# pripherals.net
KiCad netlist of a schematic drawn in Altium Designer
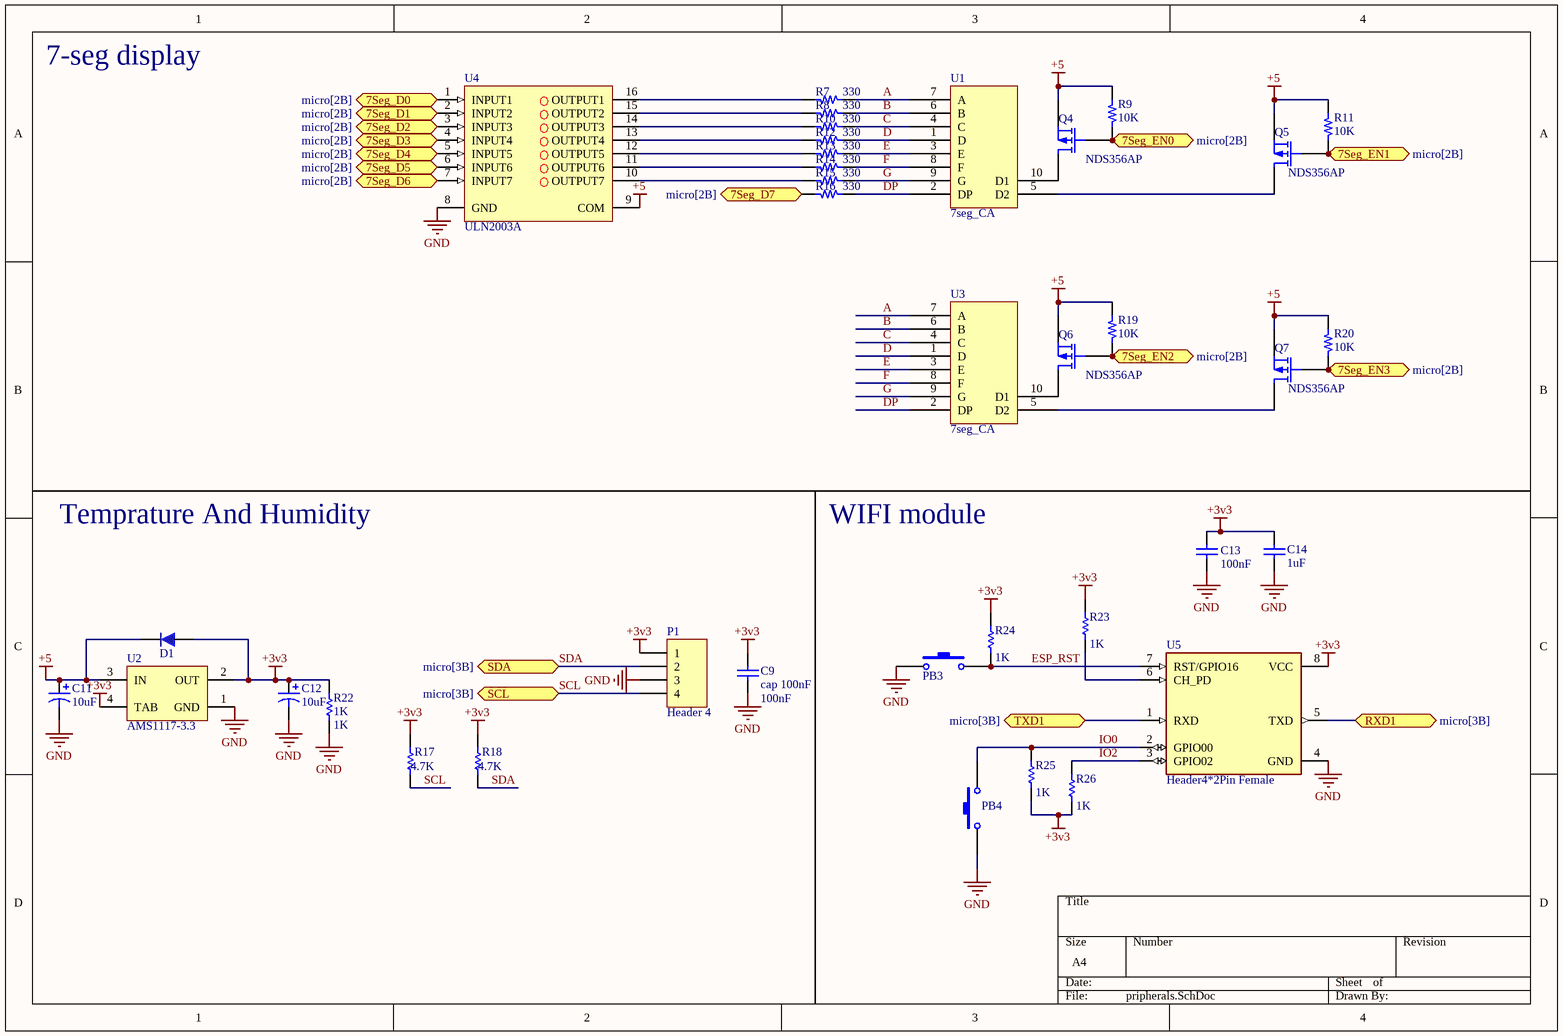
[diagram p0: pripherals.SchDoc]

(export (version "E")
  (design (tool "Eeschema 10.0.6"))
  (components
    (comp (ref "C9")
      (value "cap 100nF")
      (footprint "Cap 805")
      (description "Capacitor")
      (fields (field (name "ALTIUM_VALUE") "100nF") (field (name "PUBLISHER") "Altium Limited"))
      (libsource (lib "Miscellaneous Devices") (part "Cap"))
    )
    (comp (ref "C11")
      (value "10uF")
      (footprint "CAP0805")
      (description "CAP seramic")
      (fields (field (name "Comment") "cap 10uF") (field (name "PUBLISHER") "Altium Limited"))
      (libsource (lib "Miscellaneous Devices") (part "Cap Pol1"))
    )
    (comp (ref "C12")
      (value "10uF")
      (footprint "CAP0805")
      (description "CAP seramic")
      (fields (field (name "Comment") "cap 10uF") (field (name "PUBLISHER") "Altium Limited"))
      (libsource (lib "Miscellaneous Devices") (part "Cap Pol1"))
    )
    (comp (ref "C13")
      (value "100nF")
      (footprint "CAP0805")
      (description "CAP seramic")
      (fields (field (name "Comment") "cap 100nF"))
      (libsource (lib "Altium library (www.AVRelec.com)") (part "Cap ceramic"))
    )
    (comp (ref "C14")
      (value "1uF")
      (footprint "CAP0805")
      (description "CAP seramic")
      (fields (field (name "Comment") "cap 1uF"))
      (libsource (lib "Altium library (www.AVRelec.com)") (part "Cap ceramic"))
    )
    (comp (ref "D1")
      (value "uf4007")
      (footprint "DIOM4629X24N")
      (description "Standard Rectifiers")
      (fields (field (name "MANUFACTURER") "DC COMPONENTS") (field (name "DESIGNER") "Abbas Basereh"))
      (libsource (lib "Altium (2)") (part "1n4007 SMD M7"))
    )
    (comp (ref "P1")
      (value "Header 4")
      (footprint "HDR1X4")
      (description "Header, 4-Pin")
      (fields (field (name "PUBLISHER") "Altium Limited"))
      (libsource (lib "Miscellaneous Connectors") (part "Header 4"))
    )
    (comp (ref "PB3")
      (value "Push-Button-tall")
      (footprint "tack-sw-3x5x6")
      (libsource (lib "Mine-Discreet") (part "Push-Button-tall"))
    )
    (comp (ref "PB4")
      (value "Push-Button-tall")
      (footprint "tack-sw-3x5x6")
      (libsource (lib "Mine-Discreet") (part "Push-Button-tall"))
    )
    (comp (ref "Q4")
      (value "NDS356AP")
      (footprint "soT95p280x130-3n")
      (description "P-Channel MOSFET SOT23")
      (fields (field (name "PUBLISHER") "Altium Limited"))
      (libsource (lib "Miscellaneous Devices") (part "MOSFET-P"))
    )
    (comp (ref "Q5")
      (value "NDS356AP")
      (footprint "soT95p280x130-3n")
      (description "P-Channel MOSFET SOT23")
      (fields (field (name "PUBLISHER") "Altium Limited"))
      (libsource (lib "Miscellaneous Devices") (part "MOSFET-P"))
    )
    (comp (ref "Q6")
      (value "NDS356AP")
      (footprint "soT95p280x130-3n")
      (description "P-Channel MOSFET SOT23")
      (fields (field (name "PUBLISHER") "Altium Limited"))
      (libsource (lib "Miscellaneous Devices") (part "MOSFET-P"))
    )
    (comp (ref "Q7")
      (value "NDS356AP")
      (footprint "soT95p280x130-3n")
      (description "P-Channel MOSFET SOT23")
      (fields (field (name "PUBLISHER") "Altium Limited"))
      (libsource (lib "Miscellaneous Devices") (part "MOSFET-P"))
    )
    (comp (ref "R7")
      (value "330")
      (footprint "RES0805")
      (description "RES SMD 0603")
      (fields (field (name "PART NUMBER") "RCS0805100KFKEA"))
      (libsource (lib "lamp control-ver2") (part "Resistor"))
    )
    (comp (ref "R8")
      (value "330")
      (footprint "RES0805")
      (description "RES SMD 0603")
      (fields (field (name "PART NUMBER") "RCS0805100KFKEA"))
      (libsource (lib "lamp control-ver2") (part "Resistor"))
    )
    (comp (ref "R9")
      (value "10K")
      (footprint "RES0805")
      (description "RES SMD 0603")
      (fields (field (name "PART NUMBER") "RCS0805100KFKEA"))
      (libsource (lib "lamp control-ver2") (part "Resistor"))
    )
    (comp (ref "R10")
      (value "330")
      (footprint "RES0805")
      (description "RES SMD 0603")
      (fields (field (name "PART NUMBER") "RCS0805100KFKEA"))
      (libsource (lib "lamp control-ver2") (part "Resistor"))
    )
    (comp (ref "R11")
      (value "10K")
      (footprint "RES0805")
      (description "RES SMD 0603")
      (fields (field (name "PART NUMBER") "RCS0805100KFKEA"))
      (libsource (lib "lamp control-ver2") (part "Resistor"))
    )
    (comp (ref "R12")
      (value "330")
      (footprint "RES0805")
      (description "RES SMD 0603")
      (fields (field (name "PART NUMBER") "RCS0805100KFKEA"))
      (libsource (lib "lamp control-ver2") (part "Resistor"))
    )
    (comp (ref "R13")
      (value "330")
      (footprint "RES0805")
      (description "RES SMD 0603")
      (fields (field (name "PART NUMBER") "RCS0805100KFKEA"))
      (libsource (lib "lamp control-ver2") (part "Resistor"))
    )
    (comp (ref "R14")
      (value "330")
      (footprint "RES0805")
      (description "RES SMD 0603")
      (fields (field (name "PART NUMBER") "RCS0805100KFKEA"))
      (libsource (lib "lamp control-ver2") (part "Resistor"))
    )
    (comp (ref "R15")
      (value "330")
      (footprint "RES0805")
      (description "RES SMD 0603")
      (fields (field (name "PART NUMBER") "RCS0805100KFKEA"))
      (libsource (lib "lamp control-ver2") (part "Resistor"))
    )
    (comp (ref "R16")
      (value "330")
      (footprint "RES0805")
      (description "RES SMD 0603")
      (fields (field (name "PART NUMBER") "RCS0805100KFKEA"))
      (libsource (lib "lamp control-ver2") (part "Resistor"))
    )
    (comp (ref "R17")
      (value "4.7K")
      (footprint "RES0805")
      (description "Resistor")
      (fields (field (name "Comment") "Res 4.7K") (field (name "PUBLISHER") "Altium Limited"))
      (libsource (lib "Miscellaneous Devices") (part "Res1"))
    )
    (comp (ref "R18")
      (value "4.7K")
      (footprint "RES0805")
      (description "Resistor")
      (fields (field (name "Comment") "Res 4.7K") (field (name "PUBLISHER") "Altium Limited"))
      (libsource (lib "Miscellaneous Devices") (part "Res1"))
    )
    (comp (ref "R19")
      (value "10K")
      (footprint "RES0805")
      (description "RES SMD 0603")
      (fields (field (name "PART NUMBER") "RCS0805100KFKEA"))
      (libsource (lib "lamp control-ver2") (part "Resistor"))
    )
    (comp (ref "R20")
      (value "10K")
      (footprint "RES0805")
      (description "RES SMD 0603")
      (fields (field (name "PART NUMBER") "RCS0805100KFKEA"))
      (libsource (lib "lamp control-ver2") (part "Resistor"))
    )
    (comp (ref "R22")
      (value "1K")
      (footprint "RES0805")
      (description "Resistor")
      (fields (field (name "ALTIUM_VALUE") "1K") (field (name "PUBLISHER") "Altium Limited"))
      (libsource (lib "Miscellaneous Devices") (part "Res1"))
    )
    (comp (ref "R23")
      (value "1K")
      (footprint "RES0805")
      (description "Resistor")
      (fields (field (name "Comment") "Res 1K") (field (name "PUBLISHER") "Altium Limited"))
      (libsource (lib "Miscellaneous Devices") (part "Res1"))
    )
    (comp (ref "R24")
      (value "1K")
      (footprint "RES0805")
      (description "Resistor")
      (fields (field (name "Comment") "Res 1K") (field (name "PUBLISHER") "Altium Limited"))
      (libsource (lib "Miscellaneous Devices") (part "Res1"))
    )
    (comp (ref "R25")
      (value "1K")
      (footprint "RES0805")
      (description "Resistor")
      (fields (field (name "Comment") "Res 1K") (field (name "PUBLISHER") "Altium Limited"))
      (libsource (lib "Miscellaneous Devices") (part "Res1"))
    )
    (comp (ref "R26")
      (value "1K")
      (footprint "RES0805")
      (description "Resistor")
      (fields (field (name "Comment") "Res 1K") (field (name "PUBLISHER") "Altium Limited"))
      (libsource (lib "Miscellaneous Devices") (part "Res1"))
    )
    (comp (ref "U1") (value "7seg_CA") (footprint "7seg") (libsource (lib "Schlib1") (part "7Seg-2digit-ca")))
    (comp (ref "U2")
      (value "AMS1117-3.3")
      (footprint "SOT223")
      (description "x.x Volt, 800mA Low-Dropout Linear Regulator, 4-pin SOT-223")
      (fields (field (name "DESIGNER") "Ali Hafizi"))
      (libsource (lib "Altium (2)") (part "AMS1117-x.x"))
    )
    (comp (ref "U3") (value "7seg_CA") (footprint "7seg") (libsource (lib "Schlib1") (part "7Seg-2digit-ca")))
    (comp (ref "U4")
      (value "ULN2003A")
      (footprint "SO16_N")
      (description "SEVEN DARLINGTON ARRAYS")
      (fields (field (name "PUBLISHER") "Abbas Basereh"))
      (libsource (lib "Altium (2)") (part "ULN2003A"))
    )
    (comp (ref "U5")
      (value "Header4*2Pin Female")
      (footprint "ESP8266-01/ESP-01")
      (description "ESP-01 wifi module")
      (fields (field (name "MP") "ESP8266-01/ESP-01") (field (name "MF") "AI-Thinker"))
      (libsource (lib "Schlib1") (part "ESP8266-01/ESP-01"))
    )
  )
  (nets
    (net (code "1") (name "+3v3") (class "Default")
      (node (ref "C12") (pin "1") (pinfunction "1_1") (pintype "passive"))
      (node (ref "C13") (pin "2") (pinfunction "2_2") (pintype "passive"))
      (node (ref "C14") (pin "1") (pinfunction "1_1") (pintype "passive"))
      (node (ref "C9") (pin "2") (pinfunction "2_2") (pintype "passive"))
      (node (ref "D1") (pin "1") (pintype "passive"))
      (node (ref "P1") (pin "1") (pinfunction "1_1") (pintype "passive"))
      (node (ref "R17") (pin "1") (pinfunction "1_1") (pintype "passive"))
      (node (ref "R18") (pin "1") (pinfunction "1_1") (pintype "passive"))
      (node (ref "R22") (pin "2") (pinfunction "2_2") (pintype "passive"))
      (node (ref "R23") (pin "1") (pinfunction "1_1") (pintype "passive"))
      (node (ref "R24") (pin "1") (pinfunction "1_1") (pintype "passive"))
      (node (ref "R25") (pin "2") (pinfunction "2_2") (pintype "passive"))
      (node (ref "R26") (pin "2") (pinfunction "2_2") (pintype "passive"))
      (node (ref "U2") (pin "2") (pinfunction "OUT_2") (pintype "power_in"))
      (node (ref "U2") (pin "4") (pinfunction "TAB_4") (pintype "power_in"))
      (node (ref "U5") (pin "8") (pinfunction "VCC_8") (pintype "power_in"))
    )
    (net (code "2") (name "+5") (class "Default")
      (node (ref "C11") (pin "1") (pinfunction "1_1") (pintype "passive"))
      (node (ref "D1") (pin "2") (pintype "passive"))
      (node (ref "Q4") (pin "3") (pinfunction "S_3") (pintype "passive"))
      (node (ref "Q5") (pin "3") (pinfunction "S_3") (pintype "passive"))
      (node (ref "Q6") (pin "3") (pinfunction "S_3") (pintype "passive"))
      (node (ref "Q7") (pin "3") (pinfunction "S_3") (pintype "passive"))
      (node (ref "R11") (pin "1") (pinfunction "1_1") (pintype "passive"))
      (node (ref "R19") (pin "1") (pinfunction "1_1") (pintype "passive"))
      (node (ref "R20") (pin "1") (pinfunction "1_1") (pintype "passive"))
      (node (ref "R9") (pin "1") (pinfunction "1_1") (pintype "passive"))
      (node (ref "U2") (pin "3") (pinfunction "IN_3") (pintype "power_in"))
      (node (ref "U4") (pin "9") (pinfunction "COM_9") (pintype "power_in"))
    )
    (net (code "3") (name "/7Seg_D0") (class "Default")
      (node (ref "U4") (pin "1") (pinfunction "INPUT1_1") (pintype "input"))
    )
    (net (code "4") (name "/7Seg_D1") (class "Default")
      (node (ref "U4") (pin "2") (pinfunction "INPUT2_2") (pintype "input"))
    )
    (net (code "5") (name "/7Seg_D2") (class "Default")
      (node (ref "U4") (pin "3") (pinfunction "INPUT3_3") (pintype "input"))
    )
    (net (code "6") (name "/7Seg_D3") (class "Default")
      (node (ref "U4") (pin "4") (pinfunction "INPUT4_4") (pintype "input"))
    )
    (net (code "7") (name "/7Seg_D4") (class "Default")
      (node (ref "U4") (pin "5") (pinfunction "INPUT5_5") (pintype "input"))
    )
    (net (code "8") (name "/7Seg_D5") (class "Default")
      (node (ref "U4") (pin "6") (pinfunction "INPUT6_6") (pintype "input"))
    )
    (net (code "9") (name "/7Seg_D6") (class "Default")
      (node (ref "U4") (pin "7") (pinfunction "INPUT7_7") (pintype "input"))
    )
    (net (code "10") (name "/7Seg_D7") (class "Default")
      (node (ref "R16") (pin "1") (pinfunction "1_1") (pintype "passive"))
    )
    (net (code "11") (name "/7Seg_EN0") (class "Default")
      (node (ref "Q4") (pin "2") (pinfunction "G_2") (pintype "passive"))
      (node (ref "R9") (pin "2") (pinfunction "2_2") (pintype "passive"))
    )
    (net (code "12") (name "/7Seg_EN1") (class "Default")
      (node (ref "Q5") (pin "2") (pinfunction "G_2") (pintype "passive"))
      (node (ref "R11") (pin "2") (pinfunction "2_2") (pintype "passive"))
    )
    (net (code "13") (name "/7Seg_EN2") (class "Default")
      (node (ref "Q6") (pin "2") (pinfunction "G_2") (pintype "passive"))
      (node (ref "R19") (pin "2") (pinfunction "2_2") (pintype "passive"))
    )
    (net (code "14") (name "/7Seg_EN3") (class "Default")
      (node (ref "Q7") (pin "2") (pinfunction "G_2") (pintype "passive"))
      (node (ref "R20") (pin "2") (pinfunction "2_2") (pintype "passive"))
    )
    (net (code "15") (name "/A") (class "Default")
      (node (ref "R7") (pin "2") (pinfunction "2_2") (pintype "passive"))
      (node (ref "U1") (pin "7") (pinfunction "A_7") (pintype "passive"))
      (node (ref "U3") (pin "7") (pinfunction "A_7") (pintype "passive"))
    )
    (net (code "16") (name "/B") (class "Default")
      (node (ref "R8") (pin "2") (pinfunction "2_2") (pintype "passive"))
      (node (ref "U1") (pin "6") (pinfunction "B_6") (pintype "passive"))
      (node (ref "U3") (pin "6") (pinfunction "B_6") (pintype "passive"))
    )
    (net (code "17") (name "/C") (class "Default")
      (node (ref "R10") (pin "2") (pinfunction "2_2") (pintype "passive"))
      (node (ref "U1") (pin "4") (pinfunction "C_4") (pintype "passive"))
      (node (ref "U3") (pin "4") (pinfunction "C_4") (pintype "passive"))
    )
    (net (code "18") (name "/D") (class "Default")
      (node (ref "R12") (pin "2") (pinfunction "2_2") (pintype "passive"))
      (node (ref "U1") (pin "1") (pinfunction "D_1") (pintype "passive"))
      (node (ref "U3") (pin "1") (pinfunction "D_1") (pintype "passive"))
    )
    (net (code "19") (name "/DP") (class "Default")
      (node (ref "R16") (pin "2") (pinfunction "2_2") (pintype "passive"))
      (node (ref "U1") (pin "2") (pinfunction "DP_2") (pintype "passive"))
      (node (ref "U3") (pin "2") (pinfunction "DP_2") (pintype "passive"))
    )
    (net (code "20") (name "/E") (class "Default")
      (node (ref "R13") (pin "2") (pinfunction "2_2") (pintype "passive"))
      (node (ref "U1") (pin "3") (pinfunction "E_3") (pintype "passive"))
      (node (ref "U3") (pin "3") (pinfunction "E_3") (pintype "passive"))
    )
    (net (code "21") (name "/ESP_RST") (class "Default")
      (node (ref "PB3") (pin "2") (pinfunction "2_2") (pintype "passive"))
      (node (ref "R24") (pin "2") (pinfunction "2_2") (pintype "passive"))
      (node (ref "U5") (pin "7") (pinfunction "RST/GPIO16_7") (pintype "input"))
    )
    (net (code "22") (name "/F") (class "Default")
      (node (ref "R14") (pin "2") (pinfunction "2_2") (pintype "passive"))
      (node (ref "U1") (pin "8") (pinfunction "F_8") (pintype "passive"))
      (node (ref "U3") (pin "8") (pinfunction "F_8") (pintype "passive"))
    )
    (net (code "23") (name "/G") (class "Default")
      (node (ref "R15") (pin "2") (pinfunction "2_2") (pintype "passive"))
      (node (ref "U1") (pin "9") (pinfunction "G_9") (pintype "passive"))
      (node (ref "U3") (pin "9") (pinfunction "G_9") (pintype "passive"))
    )
    (net (code "24") (name "/IO0") (class "Default")
      (node (ref "PB4") (pin "2") (pinfunction "2_2") (pintype "passive"))
      (node (ref "R25") (pin "1") (pinfunction "1_1") (pintype "passive"))
      (node (ref "U5") (pin "2") (pinfunction "GPIO00_2") (pintype "bidirectional"))
    )
    (net (code "25") (name "/IO2") (class "Default")
      (node (ref "R26") (pin "1") (pinfunction "1_1") (pintype "passive"))
      (node (ref "U5") (pin "3") (pinfunction "GPIO02_3") (pintype "bidirectional"))
    )
    (net (code "26") (name "/RXD1") (class "Default")
      (node (ref "U5") (pin "5") (pinfunction "TXD_5") (pintype "output"))
    )
    (net (code "27") (name "/SCL") (class "Default")
      (node (ref "P1") (pin "4") (pinfunction "4_4") (pintype "passive"))
      (node (ref "R17") (pin "2") (pinfunction "2_2") (pintype "passive"))
    )
    (net (code "28") (name "/SDA") (class "Default")
      (node (ref "P1") (pin "2") (pinfunction "2_2") (pintype "passive"))
      (node (ref "R18") (pin "2") (pinfunction "2_2") (pintype "passive"))
    )
    (net (code "29") (name "/TXD1") (class "Default")
      (node (ref "U5") (pin "1") (pinfunction "RXD_1") (pintype "input"))
    )
    (net (code "30") (name "GND") (class "Default")
      (node (ref "C11") (pin "2") (pinfunction "2_2") (pintype "passive"))
      (node (ref "C12") (pin "2") (pinfunction "2_2") (pintype "passive"))
      (node (ref "C13") (pin "1") (pinfunction "1_1") (pintype "passive"))
      (node (ref "C14") (pin "2") (pinfunction "2_2") (pintype "passive"))
      (node (ref "C9") (pin "1") (pinfunction "1_1") (pintype "passive"))
      (node (ref "P1") (pin "3") (pinfunction "3_3") (pintype "passive"))
      (node (ref "PB3") (pin "1") (pinfunction "1_1") (pintype "passive"))
      (node (ref "PB4") (pin "1") (pinfunction "1_1") (pintype "passive"))
      (node (ref "R22") (pin "1") (pinfunction "1_1") (pintype "passive"))
      (node (ref "U2") (pin "1") (pinfunction "GND_1") (pintype "power_in"))
      (node (ref "U4") (pin "8") (pinfunction "GND_8") (pintype "power_in"))
      (node (ref "U5") (pin "4") (pinfunction "GND_4") (pintype "power_in"))
    )
    (net (code "31") (name "Net-(Q4-D)") (class "Default")
      (node (ref "Q4") (pin "1") (pinfunction "D_1") (pintype "passive"))
      (node (ref "U1") (pin "10") (pinfunction "D1_10") (pintype "passive"))
    )
    (net (code "32") (name "Net-(Q5-D)") (class "Default")
      (node (ref "Q5") (pin "1") (pinfunction "D_1") (pintype "passive"))
      (node (ref "U1") (pin "5") (pinfunction "D2_5") (pintype "passive"))
    )
    (net (code "33") (name "Net-(Q6-D)") (class "Default")
      (node (ref "Q6") (pin "1") (pinfunction "D_1") (pintype "passive"))
      (node (ref "U3") (pin "10") (pinfunction "D1_10") (pintype "passive"))
    )
    (net (code "34") (name "Net-(Q7-D)") (class "Default")
      (node (ref "Q7") (pin "1") (pinfunction "D_1") (pintype "passive"))
      (node (ref "U3") (pin "5") (pinfunction "D2_5") (pintype "passive"))
    )
    (net (code "35") (name "Net-(U4-OUTPUT1)") (class "Default")
      (node (ref "R7") (pin "1") (pinfunction "1_1") (pintype "passive"))
      (node (ref "U4") (pin "16") (pinfunction "OUTPUT1_16") (pintype "passive"))
    )
    (net (code "36") (name "Net-(U4-OUTPUT2)") (class "Default")
      (node (ref "R8") (pin "1") (pinfunction "1_1") (pintype "passive"))
      (node (ref "U4") (pin "15") (pinfunction "OUTPUT2_15") (pintype "passive"))
    )
    (net (code "37") (name "Net-(U4-OUTPUT3)") (class "Default")
      (node (ref "R10") (pin "1") (pinfunction "1_1") (pintype "passive"))
      (node (ref "U4") (pin "14") (pinfunction "OUTPUT3_14") (pintype "passive"))
    )
    (net (code "38") (name "Net-(U4-OUTPUT4)") (class "Default")
      (node (ref "R12") (pin "1") (pinfunction "1_1") (pintype "passive"))
      (node (ref "U4") (pin "13") (pinfunction "OUTPUT4_13") (pintype "passive"))
    )
    (net (code "39") (name "Net-(U4-OUTPUT5)") (class "Default")
      (node (ref "R13") (pin "1") (pinfunction "1_1") (pintype "passive"))
      (node (ref "U4") (pin "12") (pinfunction "OUTPUT5_12") (pintype "passive"))
    )
    (net (code "40") (name "Net-(U4-OUTPUT6)") (class "Default")
      (node (ref "R14") (pin "1") (pinfunction "1_1") (pintype "passive"))
      (node (ref "U4") (pin "11") (pinfunction "OUTPUT6_11") (pintype "passive"))
    )
    (net (code "41") (name "Net-(U4-OUTPUT7)") (class "Default")
      (node (ref "R15") (pin "1") (pinfunction "1_1") (pintype "passive"))
      (node (ref "U4") (pin "10") (pinfunction "OUTPUT7_10") (pintype "passive"))
    )
    (net (code "42") (name "Net-(U5-CH_PD)") (class "Default")
      (node (ref "R23") (pin "2") (pinfunction "2_2") (pintype "passive"))
      (node (ref "U5") (pin "6") (pinfunction "CH_PD_6") (pintype "input"))
    )
  )
)
